# SensWear_Power.net
KiCad netlist of a schematic drawn in Altium Designer
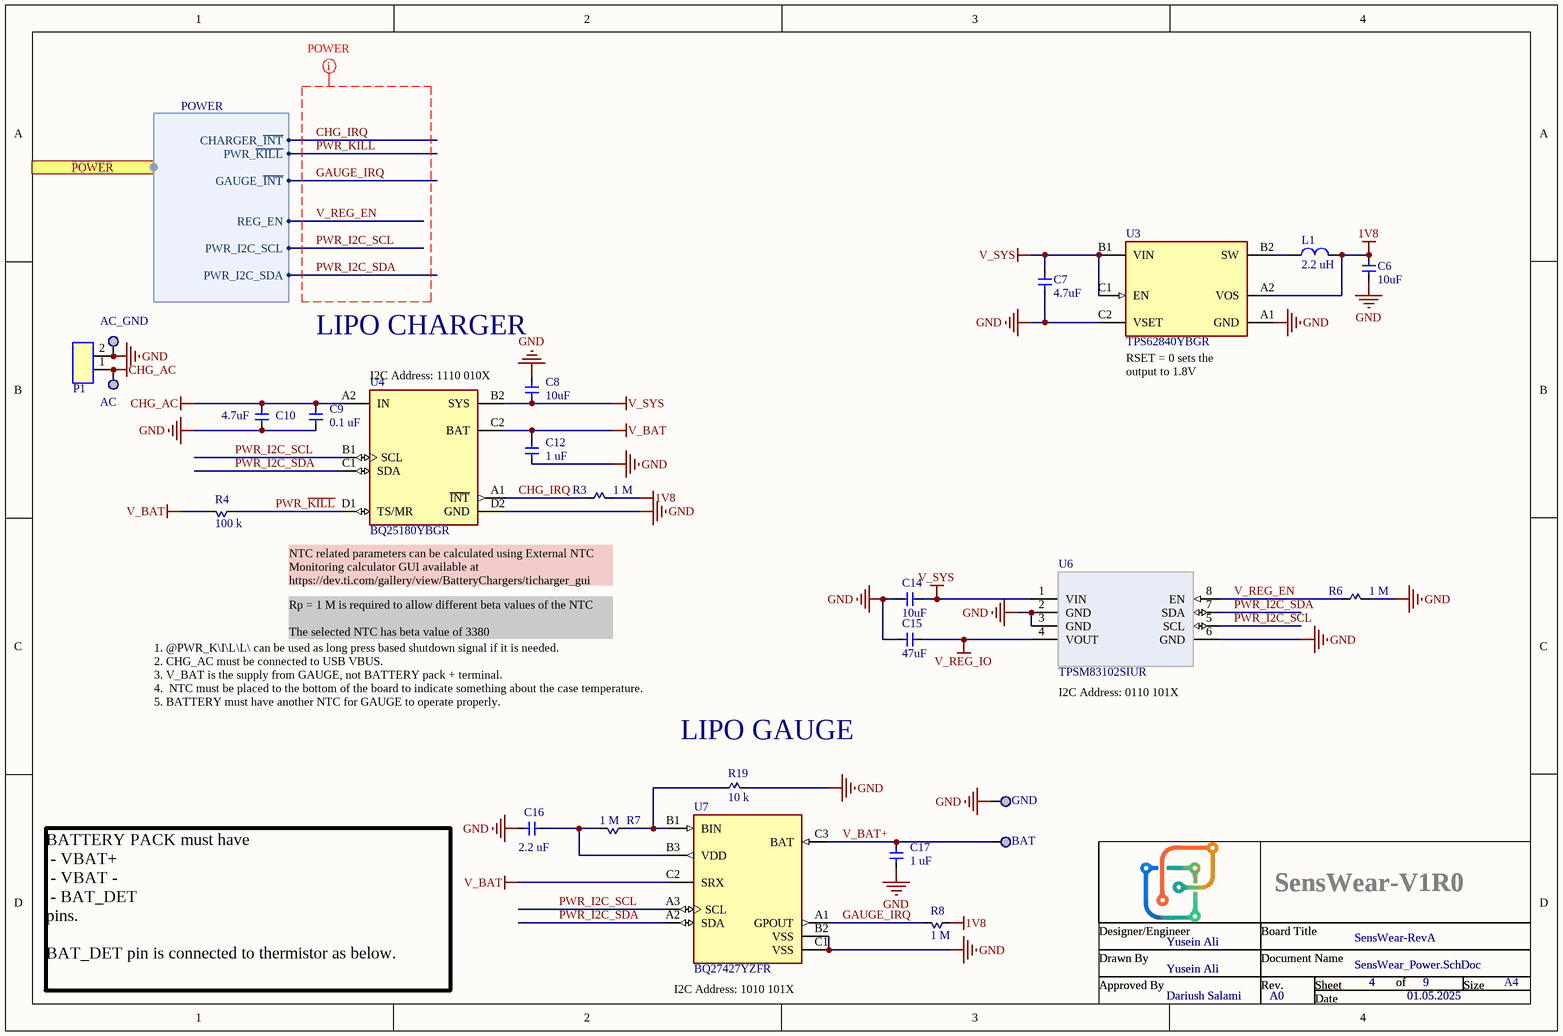
[diagram p0: SensWear_Power.SchDoc]

(export (version "E")
  (design (tool "Eeschema 10.0.6"))
  (components
    (comp (ref "AC")
      (value "TESTPAD")
      (footprint "TEST_PAD")
      (description "TESTPOINT PIN SMD")
      (libsource (lib "OpenRingComponents") (part "TESTPAD"))
    )
    (comp (ref "AC_GND")
      (value "TESTPAD")
      (footprint "TEST_PAD")
      (description "TESTPOINT PIN SMD")
      (libsource (lib "OpenRingComponents") (part "TESTPAD"))
    )
    (comp (ref "BAT")
      (value "TESTPAD")
      (footprint "TEST_PAD")
      (description "TESTPOINT PIN SMD")
      (libsource (lib "OpenRingComponents") (part "TESTPAD"))
    )
    (comp (ref "C6")
      (value "10uF")
      (footprint "CAPC1005X05N")
      (description "Multilayer Ceramic Capacitor, 10 uF, 10 V, ± 20%, X5R, 0402 [1005 Metric]")
      (fields
        (field (name "MANUFACTURER") "Samsung")
        (field (name "MANUFACTURER PART NUMBER") "CL05A106MP5NUNC")
      )
      (libsource (lib "OpenRingComponents") (part "CL05A106MP5NUNC"))
    )
    (comp (ref "C7")
      (value "4.7uF")
      (footprint "CAPC1005X05N")
      (description "Multilayer Ceramic Capacitor, 4.7 uF, 10 V, ± 20%, X5R, 0402 [1005 Metric]")
      (fields
        (field (name "MANUFACTURER") "Murata")
        (field (name "MANUFACTURER PART NUMBER") "GRM155R61A475MEAAD")
      )
      (libsource (lib "OpenRingComponents") (part "GRM155R61A475MEAAD"))
    )
    (comp (ref "C8")
      (value "10uF")
      (footprint "CAPC1005X05N")
      (description "Multilayer Ceramic Capacitor, 10 uF, 10 V, ± 20%, X5R, 0402 [1005 Metric]")
      (fields
        (field (name "MANUFACTURER") "Samsung")
        (field (name "MANUFACTURER PART NUMBER") "CL05A106MP5NUNC")
      )
      (libsource (lib "OpenRingComponents") (part "CL05A106MP5NUNC"))
    )
    (comp (ref "C9")
      (value "0.1 uF")
      (footprint "CAPC1005X05N")
      (description "CAP CER 0.1UF 16V X5R 0402")
      (fields
        (field (name "MANUFACTURER") "Murata Electronics")
        (field (name "MANUFACTURER PART NUMBER") "GRM155R61C104KA88D")
      )
      (libsource (lib "OpenRingComponents") (part "GRM155R61C104KA88D"))
    )
    (comp (ref "C10")
      (value "4.7uF")
      (footprint "CAPC1005X05N")
      (description "Multilayer Ceramic Capacitor, 4.7 uF, 10 V, ± 20%, X5R, 0402 [1005 Metric]")
      (fields
        (field (name "MANUFACTURER") "Murata")
        (field (name "MANUFACTURER PART NUMBER") "GRM155R61A475MEAAD")
      )
      (libsource (lib "OpenRingComponents") (part "GRM155R61A475MEAAD"))
    )
    (comp (ref "C12")
      (value "1 uF")
      (footprint "CAPC1005X05N")
      (description "CAP CER 1UF 10V X5R 0402")
      (fields
        (field (name "MANUFACTURER") "Murata Electronics North America")
        (field (name "MANUFACTURER PART NUMBER") "GRM155R61A105KE15D")
      )
      (libsource (lib "OpenRingComponents") (part "GRM155R61A105KE15D"))
    )
    (comp (ref "C14")
      (value "10uF")
      (footprint "CAPC1005X05N")
      (description "Multilayer Ceramic Capacitor, 10 uF, 10 V, ± 20%, X5R, 0402 [1005 Metric]")
      (fields
        (field (name "MANUFACTURER") "Samsung")
        (field (name "MANUFACTURER PART NUMBER") "CL05A106MP5NUNC")
      )
      (libsource (lib "OpenRingComponents") (part "CL05A106MP5NUNC"))
    )
    (comp (ref "C15")
      (value "47uF")
      (footprint "CAPC1610X05N")
      (description "CL10 Series 0603 47 uF 6.3 V ±20% Tolerance X5R Multilayer Ceramic Capacitor")
      (fields
        (field (name "MANUFACTURER") "Samsung")
        (field (name "MANUFACTURER PART NUMBER") "CL10A476MQ8QRNC")
      )
      (libsource (lib "OpenRingComponents") (part "CL10A476MQ8QRNC"))
    )
    (comp (ref "C16")
      (value "2.2 uF")
      (footprint "CAPC1005X05N")
      (description "CAP CER 2.2UF 10V X5R 0402")
      (fields
        (field (name "MANUFACTURER") "Murata Electronics North America")
        (field (name "MANUFACTURER PART NUMBER") "GRM155R61A225KE95D")
      )
      (libsource (lib "OpenRingComponents") (part "GRM155R61A225KE95D"))
    )
    (comp (ref "C17")
      (value "1 uF")
      (footprint "CAPC1005X05N")
      (description "CAP CER 1UF 10V X5R 0402")
      (fields
        (field (name "MANUFACTURER") "Murata Electronics North America")
        (field (name "MANUFACTURER PART NUMBER") "GRM155R61A105KE15D")
      )
      (libsource (lib "OpenRingComponents") (part "GRM155R61A105KE15D"))
    )
    (comp (ref "GND")
      (value "TESTPAD")
      (footprint "TEST_PAD")
      (description "TESTPOINT PIN SMD")
      (libsource (lib "OpenRingComponents") (part "TESTPAD"))
    )
    (comp (ref "L1")
      (value "2.2 uH")
      (footprint "FP-DFE201612C-MFG")
      (description "Inductor Power Shielded Wirewound 2.2uH 20% 1MHz Metal 1.8A 0.116Ohm DCR 0806 T/R")
      (fields
        (field (name "MANUFACTURER") "Murata")
        (field (name "MANUFACTURER PART NUMBER") "DFE201612E-2R2M=P2")
      )
      (libsource (lib "OpenRingComponents") (part "DFE201612E-2R2M=P2"))
    )
    (comp (ref "P1")
      (value "RM-1238-B02-41")
      (footprint "RM-1238-B02-41_2")
      (description "RM-1238-B02-41 by www.xtpogopin.com")
      (fields (field (name "MANUFACTURER") "XTPogoPin"))
      (libsource (lib "Connectors") (part "RM-1238-B02-41"))
    )
    (comp (ref "R3")
      (value "1 M")
      (footprint "RESC1005X04N")
      (description "RES SMD 1M OHM 1% 1/10W 0402")
      (fields
        (field (name "MANUFACTURER") "Panasonic Electronic Components")
        (field (name "MANUFACTURER PART NUMBER") "ERJ-2RKF1004X")
      )
      (libsource (lib "OpenRingComponents") (part "ERJ-2RKF1004X"))
    )
    (comp (ref "R4")
      (value "100 k")
      (footprint "RESC1005X04N")
      (description "RES SMD 100K OHM 1% 1/10W 0402")
      (fields
        (field (name "MANUFACTURER") "Panasonic Electronic Components")
        (field (name "MANUFACTURER PART NUMBER") "ERJ-2RKF1003X")
      )
      (libsource (lib "OpenRingComponents") (part "ERJ-2RKF1003X"))
    )
    (comp (ref "R6")
      (value "1 M")
      (footprint "RESC1005X04N")
      (description "RES SMD 1M OHM 1% 1/10W 0402")
      (fields
        (field (name "MANUFACTURER") "Panasonic Electronic Components")
        (field (name "MANUFACTURER PART NUMBER") "ERJ-2RKF1004X")
      )
      (libsource (lib "OpenRingComponents") (part "ERJ-2RKF1004X"))
    )
    (comp (ref "R7")
      (value "1 M")
      (footprint "RESC1005X04N")
      (description "RES SMD 1M OHM 1% 1/10W 0402")
      (fields
        (field (name "MANUFACTURER") "Panasonic Electronic Components")
        (field (name "MANUFACTURER PART NUMBER") "ERJ-2RKF1004X")
      )
      (libsource (lib "OpenRingComponents") (part "ERJ-2RKF1004X"))
    )
    (comp (ref "R8")
      (value "1 M")
      (footprint "RESC1005X04N")
      (description "RES SMD 1M OHM 1% 1/10W 0402")
      (fields
        (field (name "MANUFACTURER") "Panasonic Electronic Components")
        (field (name "MANUFACTURER PART NUMBER") "ERJ-2RKF1004X")
      )
      (libsource (lib "OpenRingComponents") (part "ERJ-2RKF1004X"))
    )
    (comp (ref "R19")
      (value "10 k")
      (footprint "RESC1005X04N")
      (description "RES SMD 10K OHM 1% 1/10W 0402")
      (fields
        (field (name "MANUFACTURER") "Panasonic Electronic Components")
        (field (name "MANUFACTURER PART NUMBER") "ERJ-2RKF1002X")
      )
      (libsource (lib "OpenRingComponents") (part "ERJ-2RKF1002X"))
    )
    (comp (ref "U3")
      (value "TPS62840YBGR")
      (footprint "BGA6C40P2X3_97X147X50")
      (description "Conv DC-DC 1.8V to 6.5V Synchronous Step Down Single-Out 1.8V to 3.3V 0.75A 6-Pin DSBGA T/R")
      (fields (field (name "MANUFACTURER") "Texas Instruments"))
      (libsource (lib "OpenRingComponents") (part "TPS62840YBGR"))
    )
    (comp (ref "U4")
      (value "BQ25180YBGR")
      (footprint "BGA8C40P2X4_104X159X50")
      (description "1-A Li-ion I²C programmable charger with regulated power path in WCSP package 8-DSBGA -40 to 85")
      (fields (field (name "MANUFACTURER") "Texas Instruments"))
      (libsource (lib "OpenRingComponents") (part "BQ25180YBGR"))
    )
    (comp (ref "U6")
      (value "TPSM83102SIUR")
      (footprint "MicroSiP8_SIU-A_TEX-M")
      (fields (field (name "MANUFACTURER") "Texas Instruments"))
      (libsource (lib "OpenRingComponents") (part "TPSM83102SIUR"))
    )
    (comp (ref "U7")
      (value "BQ27427YZFR")
      (footprint "BGA9C50P3X3_158X162X62")
      (fields (field (name "MANUFACTURER") "Texas Instruments"))
      (libsource (lib "OpenRingComponents") (part "BQ27427YZFR"))
    )
  )
  (nets
    (net (code "2") (name "/CHG_IRQ") (class "Default")
      (node (ref "R3") (pin "2") (pinfunction "2_2") (pintype "passive"))
      (node (ref "U4") (pin "A1") (pinfunction "~{INT}_A1") (pintype "output"))
    )
    (net (code "3") (name "/GAUGE_IRQ") (class "Default")
      (node (ref "R8") (pin "2") (pinfunction "2_2") (pintype "passive"))
      (node (ref "U7") (pin "A1") (pinfunction "GPOUT_A1") (pintype "output"))
    )
    (net (code "4") (name "/PWR_I2C_SCL") (class "Default")
      (node (ref "U4") (pin "B1") (pinfunction "SCL_B1") (pintype "bidirectional"))
      (node (ref "U6") (pin "5") (pinfunction "SCL_5") (pintype "bidirectional"))
      (node (ref "U7") (pin "A3") (pinfunction "SCL_A3") (pintype "bidirectional"))
    )
    (net (code "5") (name "/PWR_I2C_SDA") (class "Default")
      (node (ref "U4") (pin "C1") (pinfunction "SDA_C1") (pintype "bidirectional"))
      (node (ref "U6") (pin "7") (pinfunction "SDA_7") (pintype "bidirectional"))
      (node (ref "U7") (pin "A2") (pinfunction "SDA_A2") (pintype "bidirectional"))
    )
    (net (code "6") (name "/PWR_~{KILL}") (class "Default")
      (node (ref "R4") (pin "1") (pinfunction "1_1") (pintype "passive"))
      (node (ref "U4") (pin "D1") (pinfunction "TS/MR_D1") (pintype "bidirectional"))
    )
    (net (code "7") (name "/V_BAT+") (class "Default")
      (node (ref "BAT") (pin "1") (pinfunction "1_1") (pintype "passive"))
      (node (ref "C17") (pin "1") (pinfunction "1_1") (pintype "passive"))
      (node (ref "U7") (pin "C3") (pinfunction "BAT_C3") (pintype "input"))
    )
    (net (code "8") (name "/V_REG_EN") (class "Default")
      (node (ref "R6") (pin "2") (pinfunction "2_2") (pintype "passive"))
      (node (ref "U6") (pin "8") (pinfunction "EN_8") (pintype "input"))
    )
    (net (code "10") (name "1V8") (class "Default")
      (node (ref "C6") (pin "1") (pinfunction "1_1") (pintype "passive"))
      (node (ref "L1") (pin "2") (pinfunction "2_2") (pintype "passive"))
      (node (ref "R3") (pin "1") (pinfunction "1_1") (pintype "passive"))
      (node (ref "R8") (pin "1") (pinfunction "1_1") (pintype "passive"))
      (node (ref "U3") (pin "A2") (pinfunction "VOS_A2") (pintype "power_in"))
    )
    (net (code "11") (name "CHG_AC") (class "Default")
      (node (ref "AC") (pin "1") (pinfunction "1_1") (pintype "passive"))
      (node (ref "C10") (pin "2") (pinfunction "2_2") (pintype "passive"))
      (node (ref "C9") (pin "1") (pinfunction "1_1") (pintype "passive"))
      (node (ref "P1") (pin "1") (pinfunction "1_1") (pintype "passive"))
      (node (ref "U4") (pin "A2") (pinfunction "IN_A2") (pintype "power_in"))
    )
    (net (code "12") (name "GND") (class "Default")
      (node (ref "AC_GND") (pin "1") (pinfunction "1_1") (pintype "passive"))
      (node (ref "C10") (pin "1") (pinfunction "1_1") (pintype "passive"))
      (node (ref "C12") (pin "2") (pinfunction "2_2") (pintype "passive"))
      (node (ref "C14") (pin "1") (pinfunction "1_1") (pintype "passive"))
      (node (ref "C15") (pin "1") (pinfunction "1_1") (pintype "passive"))
      (node (ref "C16") (pin "2") (pinfunction "2_2") (pintype "passive"))
      (node (ref "C17") (pin "2") (pinfunction "2_2") (pintype "passive"))
      (node (ref "C6") (pin "2") (pinfunction "2_2") (pintype "passive"))
      (node (ref "C7") (pin "1") (pinfunction "1_1") (pintype "passive"))
      (node (ref "C8") (pin "2") (pinfunction "2_2") (pintype "passive"))
      (node (ref "C9") (pin "2") (pinfunction "2_2") (pintype "passive"))
      (node (ref "GND") (pin "1") (pinfunction "1_1") (pintype "passive"))
      (node (ref "P1") (pin "2") (pinfunction "2_2") (pintype "passive"))
      (node (ref "R19") (pin "2") (pinfunction "2_2") (pintype "passive"))
      (node (ref "R6") (pin "1") (pinfunction "1_1") (pintype "passive"))
      (node (ref "U3") (pin "A1") (pinfunction "GND_A1") (pintype "power_in"))
      (node (ref "U3") (pin "C2") (pinfunction "VSET_C2") (pintype "power_in"))
      (node (ref "U4") (pin "D2") (pinfunction "GND_D2") (pintype "power_in"))
      (node (ref "U6") (pin "2") (pinfunction "GND_2") (pintype "power_in"))
      (node (ref "U6") (pin "3") (pinfunction "GND_3") (pintype "power_in"))
      (node (ref "U6") (pin "6") (pinfunction "GND_6") (pintype "power_in"))
      (node (ref "U7") (pin "B2") (pinfunction "VSS_B2") (pintype "power_in"))
      (node (ref "U7") (pin "C1") (pinfunction "VSS_C1") (pintype "power_in"))
    )
    (net (code "13") (name "Net-(U3-SW)") (class "Default")
      (node (ref "L1") (pin "1") (pinfunction "1_1") (pintype "passive"))
      (node (ref "U3") (pin "B2") (pinfunction "SW_B2") (pintype "power_in"))
    )
    (net (code "14") (name "Net-(U7-BIN)") (class "Default")
      (node (ref "R19") (pin "1") (pinfunction "1_1") (pintype "passive"))
      (node (ref "R7") (pin "1") (pinfunction "1_1") (pintype "passive"))
      (node (ref "U7") (pin "B1") (pinfunction "BIN_B1") (pintype "input"))
    )
    (net (code "15") (name "Net-(U7-VDD)") (class "Default")
      (node (ref "C16") (pin "1") (pinfunction "1_1") (pintype "passive"))
      (node (ref "R7") (pin "2") (pinfunction "2_2") (pintype "passive"))
      (node (ref "U7") (pin "B3") (pinfunction "VDD_B3") (pintype "output"))
    )
    (net (code "16") (name "V_BAT") (class "Default")
      (node (ref "C12") (pin "1") (pinfunction "1_1") (pintype "passive"))
      (node (ref "R4") (pin "2") (pinfunction "2_2") (pintype "passive"))
      (node (ref "U4") (pin "C2") (pinfunction "BAT_C2") (pintype "power_in"))
      (node (ref "U7") (pin "C2") (pinfunction "SRX_C2") (pintype "power_in"))
    )
    (net (code "17") (name "V_REG_IO") (class "Default")
      (node (ref "C15") (pin "2") (pinfunction "2_2") (pintype "passive"))
      (node (ref "U6") (pin "4") (pinfunction "VOUT_4") (pintype "power_in"))
    )
    (net (code "18") (name "V_SYS") (class "Default")
      (node (ref "C14") (pin "2") (pinfunction "2_2") (pintype "passive"))
      (node (ref "C7") (pin "2") (pinfunction "2_2") (pintype "passive"))
      (node (ref "C8") (pin "1") (pinfunction "1_1") (pintype "passive"))
      (node (ref "U3") (pin "B1") (pinfunction "VIN_B1") (pintype "power_in"))
      (node (ref "U3") (pin "C1") (pinfunction "EN_C1") (pintype "input"))
      (node (ref "U4") (pin "B2") (pinfunction "SYS_B2") (pintype "power_in"))
      (node (ref "U6") (pin "1") (pinfunction "VIN_1") (pintype "power_in"))
    )
  )
)
